# amp.net
KiCad netlist of a schematic drawn in Altium Designer
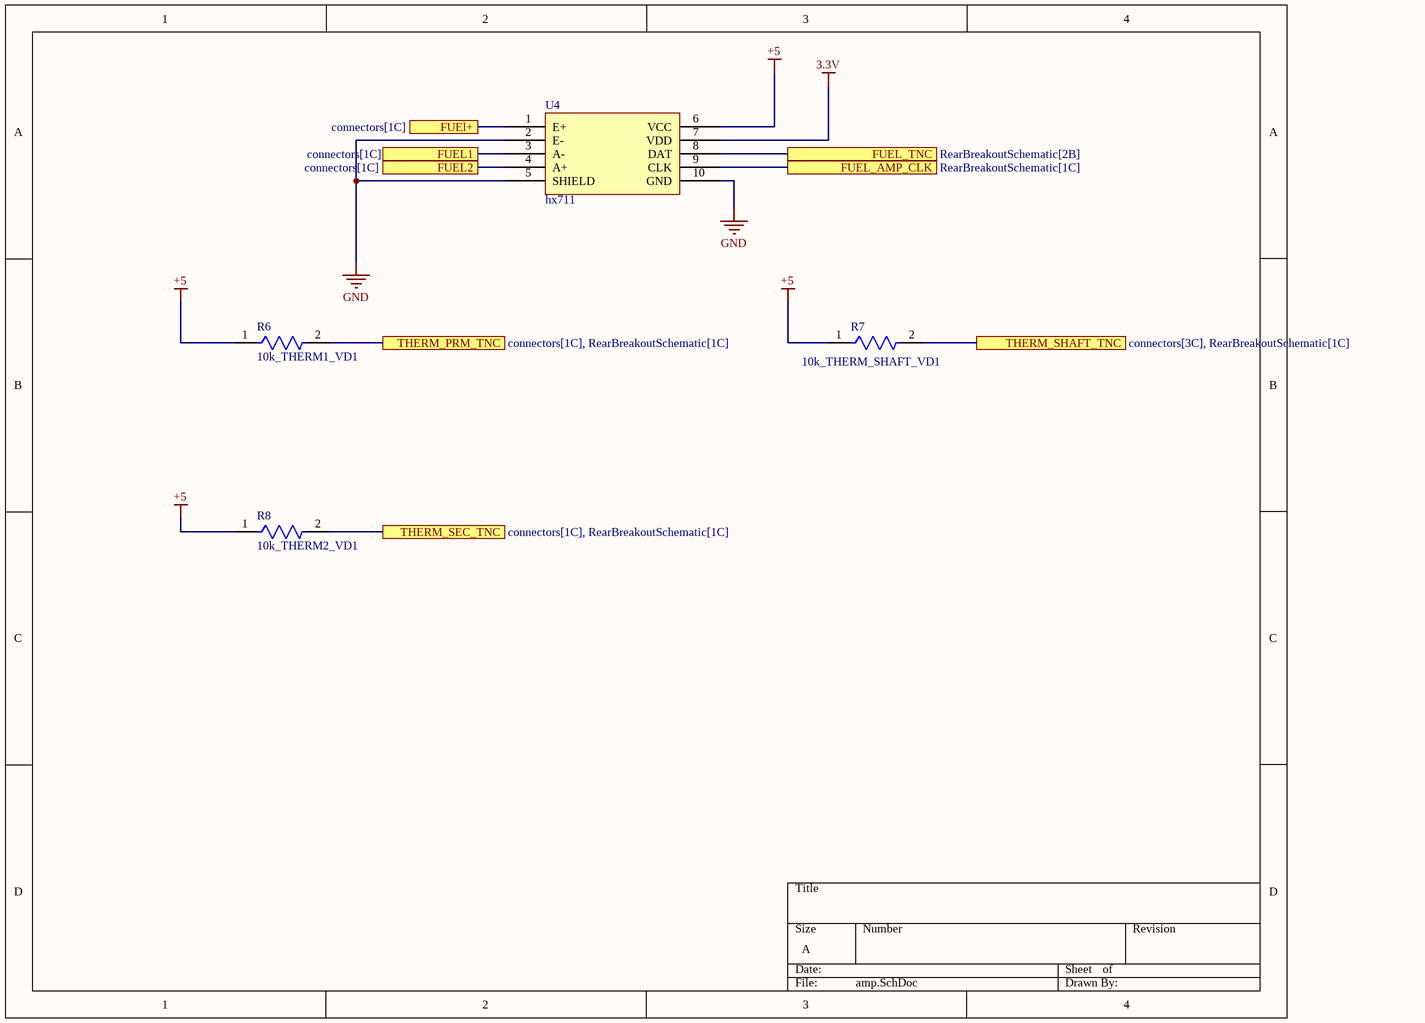
[diagram p0: amp.SchDoc]

(export (version "E")
  (design (tool "Eeschema 10.0.6"))
  (components
    (comp (ref "R6")
      (value "10k_THERM1_VD1")
      (footprint "FP-CRCW0805-e3-IPC_C")
      (description "RES Thick Film, 4.02Ω, 1%, 0.125W, 200ppm/°C, 0805")
      (fields (field (name "TOLERANCE") "1%"))
      (libsource (lib "Altium Content Vault") (part "1029c3af85768c4190bb7ad29bc67b5"))
    )
    (comp (ref "R7")
      (value "10k_THERM_SHAFT_VD1")
      (footprint "FP-CRCW0805-e3-IPC_C")
      (description "RES Thick Film, 4.02Ω, 1%, 0.125W, 200ppm/°C, 0805")
      (fields (field (name "TOLERANCE") "1%"))
      (libsource (lib "Altium Content Vault") (part "1029c3af85768c4190bb7ad29bc67b5"))
    )
    (comp (ref "R8")
      (value "10k_THERM2_VD1")
      (footprint "FP-CRCW0805-e3-IPC_C")
      (description "RES Thick Film, 4.02Ω, 1%, 0.125W, 200ppm/°C, 0805")
      (fields (field (name "TOLERANCE") "1%"))
      (libsource (lib "Altium Content Vault") (part "1029c3af85768c4190bb7ad29bc67b5"))
    )
    (comp (ref "U4")
      (value "hx711")
      (footprint "PCBComponent_1")
      (libsource (lib "HX711LIB") (part "Component_1"))
    )
  )
  (nets
    (net (code "1") (name "+5") (class "Default")
      (node (ref "R6") (pin "1") (pinfunction "1_1") (pintype "passive"))
      (node (ref "R7") (pin "1") (pinfunction "1_1") (pintype "passive"))
      (node (ref "R8") (pin "1") (pinfunction "1_1") (pintype "passive"))
      (node (ref "U4") (pin "6") (pinfunction "VCC_6") (pintype "passive"))
    )
    (net (code "2") (name "/FUEL1") (class "Default")
      (node (ref "U4") (pin "3") (pinfunction "A-_3") (pintype "passive"))
    )
    (net (code "3") (name "/FUEL2") (class "Default")
      (node (ref "U4") (pin "4") (pinfunction "A+_4") (pintype "passive"))
    )
    (net (code "4") (name "/FUEL_AMP_CLK") (class "Default")
      (node (ref "U4") (pin "9") (pinfunction "CLK_9") (pintype "passive"))
    )
    (net (code "5") (name "/FUEL_TNC") (class "Default")
      (node (ref "U4") (pin "8") (pinfunction "DAT_8") (pintype "passive"))
    )
    (net (code "6") (name "/FUEl+") (class "Default")
      (node (ref "U4") (pin "1") (pinfunction "E+_1") (pintype "passive"))
    )
    (net (code "7") (name "/THERM_PRM_TNC") (class "Default")
      (node (ref "R6") (pin "2") (pinfunction "2_2") (pintype "passive"))
    )
    (net (code "8") (name "/THERM_SEC_TNC") (class "Default")
      (node (ref "R8") (pin "2") (pinfunction "2_2") (pintype "passive"))
    )
    (net (code "9") (name "/THERM_SHAFT_TNC") (class "Default")
      (node (ref "R7") (pin "2") (pinfunction "2_2") (pintype "passive"))
    )
    (net (code "10") (name "3.3V") (class "Default")
      (node (ref "U4") (pin "7") (pinfunction "VDD_7") (pintype "passive"))
    )
    (net (code "11") (name "GND") (class "Default")
      (node (ref "U4") (pin "10") (pinfunction "GND_10") (pintype "passive"))
      (node (ref "U4") (pin "2") (pinfunction "E-_2") (pintype "passive"))
      (node (ref "U4") (pin "5") (pinfunction "SHIELD_5") (pintype "passive"))
    )
  )
)
